# dengen1_2.net
KiCad netlist of a schematic drawn in EAGLE
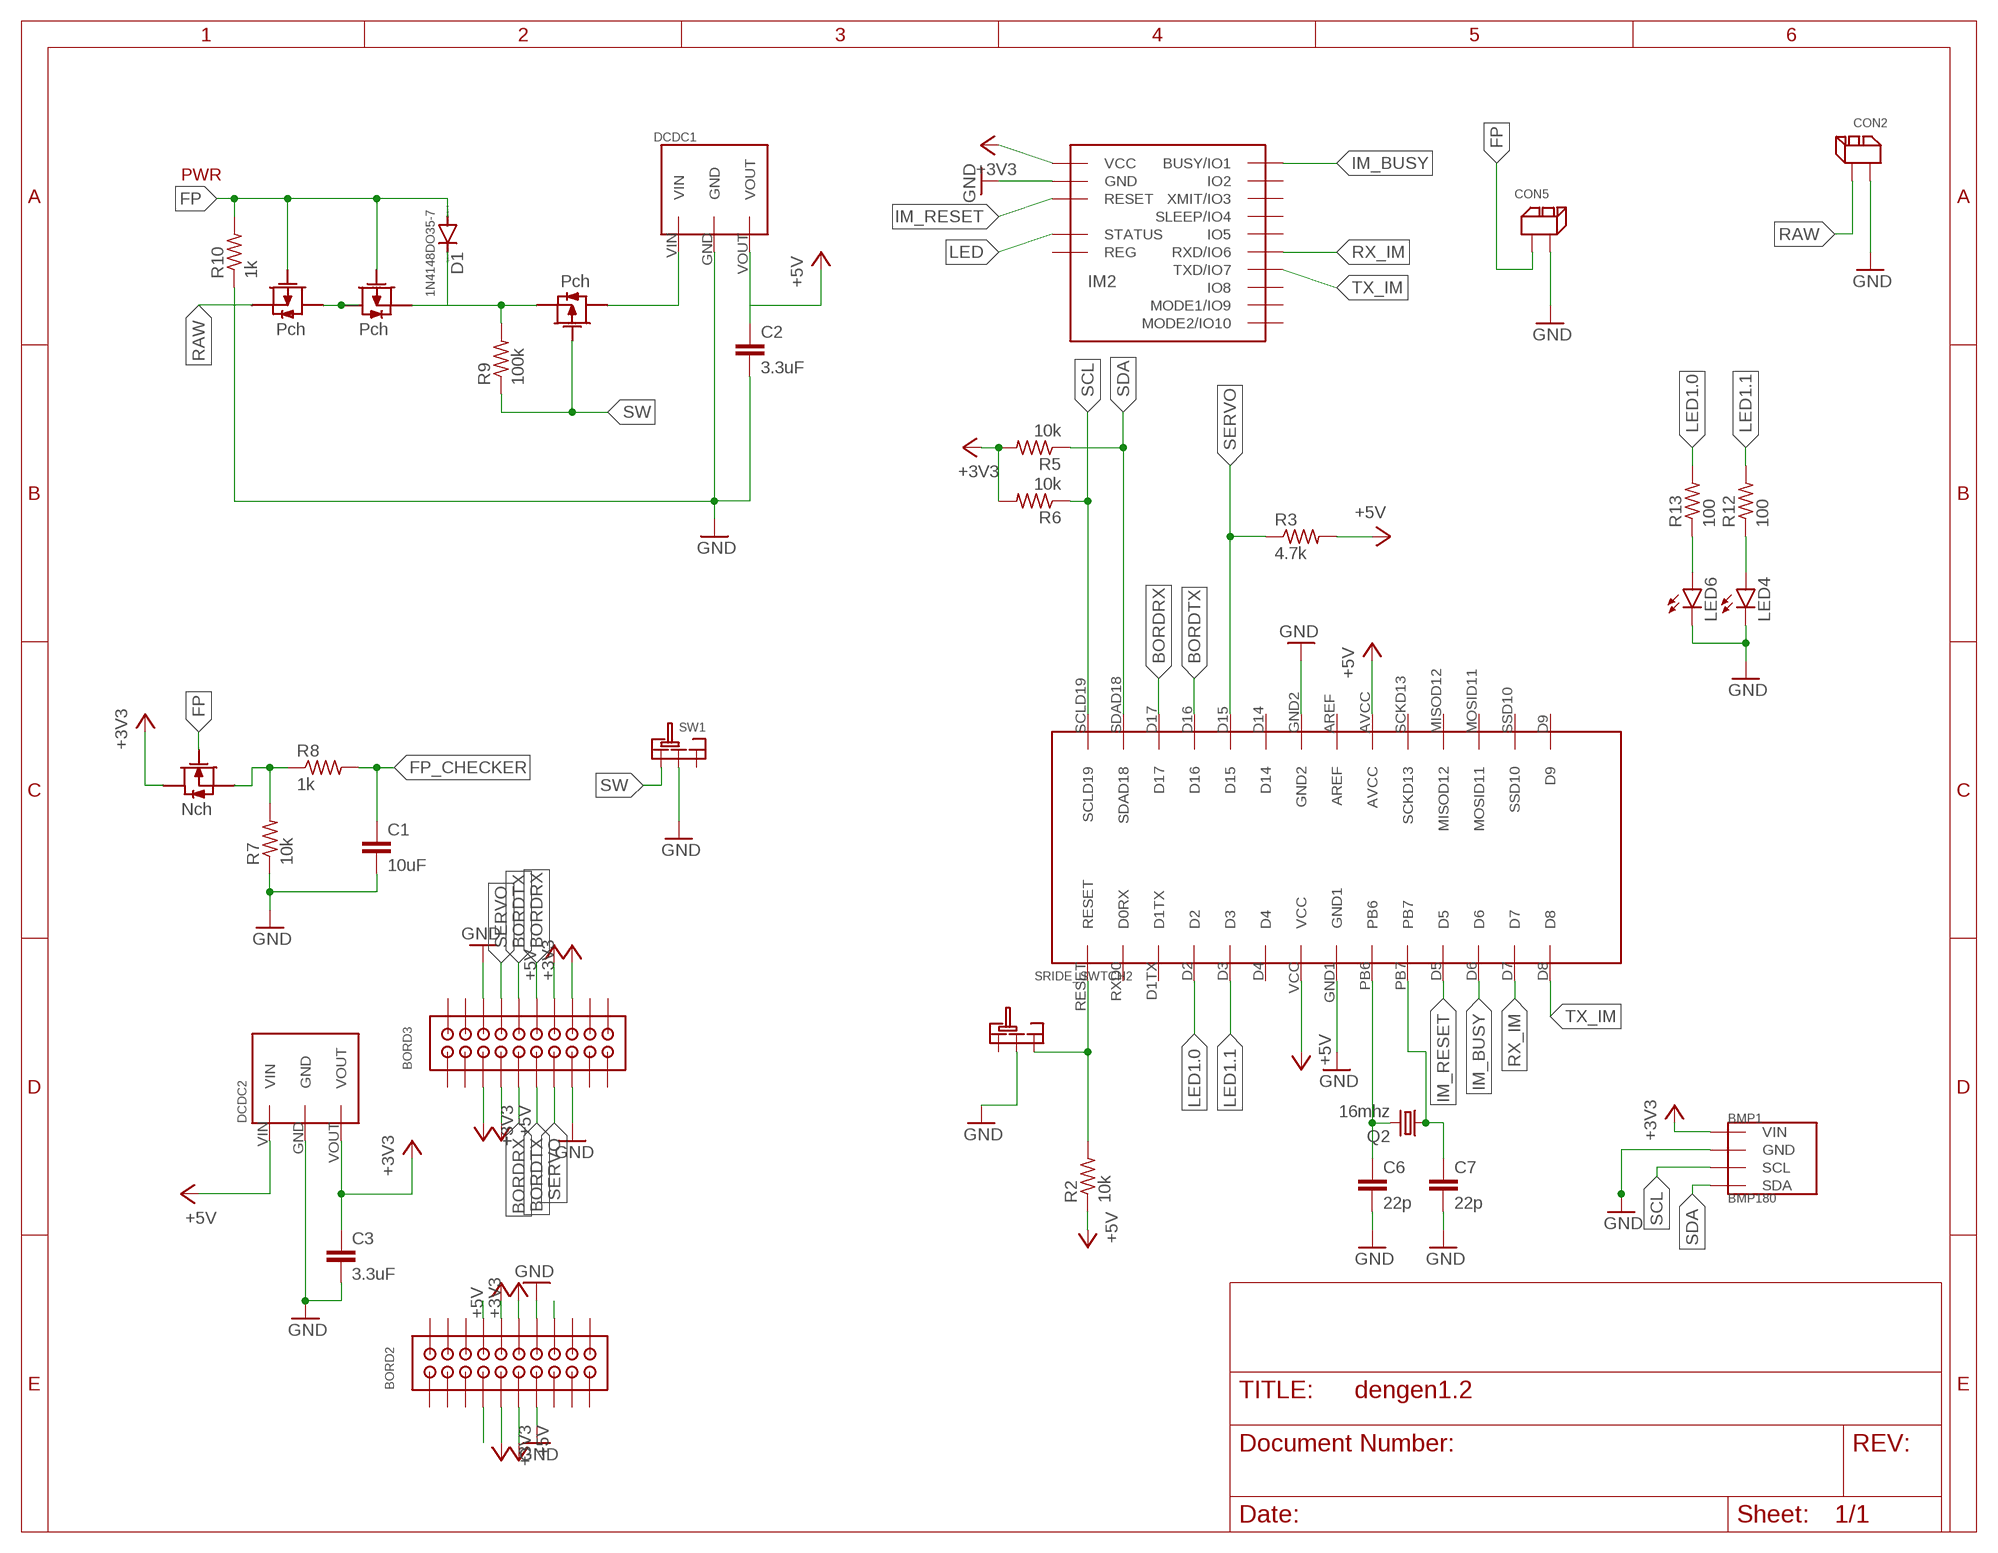
[diagram p0: schematic, sheet 1]

(export (version "E")
  (design (tool "Eeschema 10.0.6"))
  (components
    (comp (ref "BMP1")
      (value "BMP180")
      (footprint "eagle-import:GY-68")
      (libsource (lib "eagle-import") (part "BMP180"))
    )
    (comp (ref "BORD2")
      (value "2X10")
      (footprint "eagle-import:2X10")
      (libsource (lib "eagle-import") (part "2X10"))
    )
    (comp (ref "BORD3")
      (value "2X10")
      (footprint "eagle-import:2X10")
      (libsource (lib "eagle-import") (part "2X10"))
    )
    (comp (ref "C1")
      (value "10uF")
      (footprint "eagle-import:C025-024X044")
      (libsource (lib "eagle-import") (part "C-EU025-024X044"))
    )
    (comp (ref "C2")
      (value "3.3uF")
      (footprint "eagle-import:C025-024X044")
      (libsource (lib "eagle-import") (part "C-EU025-024X044"))
    )
    (comp (ref "C3")
      (value "3.3uF")
      (footprint "eagle-import:C025-024X044")
      (libsource (lib "eagle-import") (part "C-EU025-024X044"))
    )
    (comp (ref "C6")
      (value "22p")
      (footprint "eagle-import:C025-024X044")
      (libsource (lib "eagle-import") (part "C-EU025-024X044"))
    )
    (comp (ref "C7")
      (value "22p")
      (footprint "eagle-import:C025-024X044")
      (libsource (lib "eagle-import") (part "C-EU025-024X044"))
    )
    (comp (ref "CON2")
      (value "2PIN")
      (footprint "eagle-import:2PIN")
      (libsource (lib "eagle-import") (part "2PIN"))
    )
    (comp (ref "CON5")
      (value "2PIN")
      (footprint "eagle-import:2PIN")
      (libsource (lib "eagle-import") (part "2PIN"))
    )
    (comp (ref "D1")
      (value "1N4148DO35-7")
      (footprint "eagle-import:DO35-7")
      (libsource (lib "eagle-import") (part "1N4148DO35-7"))
    )
    (comp (ref "DCDC1")
      (value "5V1A_M78AR05-1")
      (footprint "eagle-import:5V1A_M78AR05-1")
      (libsource (lib "eagle-import") (part "5V1A_M78AR05-1"))
    )
    (comp (ref "DCDC2")
      (value "3.3V1A_M78AR033-1")
      (footprint "eagle-import:3.3V1A_M78AR033-1")
      (libsource (lib "eagle-import") (part "3.3V1A_M78AR033-1"))
    )
    (comp (ref "IM2")
      (value "IM920_IM920C")
      (footprint "eagle-import:IM920_IM920C")
      (libsource (lib "eagle-import") (part "IM920_IM920C"))
    )
    (comp (ref "LED4")
      (value "LED5MM")
      (footprint "eagle-import:LED5MM")
      (libsource (lib "eagle-import") (part "LED5MM"))
    )
    (comp (ref "LED6")
      (value "LED5MM")
      (footprint "eagle-import:LED5MM")
      (libsource (lib "eagle-import") (part "LED5MM"))
    )
    (comp (ref "Q2")
      (value "16mhz")
      (footprint "eagle-import:HC49_S")
      (libsource (lib "eagle-import") (part "CRYSTALHC49S"))
    )
    (comp (ref "R2")
      (value "10k")
      (footprint "eagle-import:0204_7")
      (libsource (lib "eagle-import") (part "R-US_0204/7"))
    )
    (comp (ref "R3")
      (value "4.7k")
      (footprint "eagle-import:0204_7")
      (libsource (lib "eagle-import") (part "R-US_0204/7"))
    )
    (comp (ref "R5")
      (value "10k")
      (footprint "eagle-import:0204_7")
      (libsource (lib "eagle-import") (part "R-US_0204/7"))
    )
    (comp (ref "R6")
      (value "10k")
      (footprint "eagle-import:0204_7")
      (libsource (lib "eagle-import") (part "R-US_0204/7"))
    )
    (comp (ref "R7")
      (value "10k")
      (footprint "eagle-import:0204_7")
      (libsource (lib "eagle-import") (part "R-US_0204/7"))
    )
    (comp (ref "R8")
      (value "1k")
      (footprint "eagle-import:0204_7")
      (libsource (lib "eagle-import") (part "R-US_0204/7"))
    )
    (comp (ref "R9")
      (value "100k")
      (footprint "eagle-import:0204_7")
      (libsource (lib "eagle-import") (part "R-US_0204/7"))
    )
    (comp (ref "R10")
      (value "1k")
      (footprint "eagle-import:0204_7")
      (libsource (lib "eagle-import") (part "R-US_0204/7"))
    )
    (comp (ref "R12")
      (value "100")
      (footprint "eagle-import:0204_7")
      (libsource (lib "eagle-import") (part "R-US_0204/7"))
    )
    (comp (ref "R13")
      (value "100")
      (footprint "eagle-import:0204_7")
      (libsource (lib "eagle-import") (part "R-US_0204/7"))
    )
    (comp (ref "SRIDE_SWTCH2")
      (value "SRIDE_SWITCH")
      (footprint "eagle-import:SRIDE_SWITCH")
      (libsource (lib "eagle-import") (part "SRIDE_SWITCH"))
    )
    (comp (ref "SW1")
      (value "SRIDE_SWITCH")
      (footprint "eagle-import:SRIDE_SWITCH")
      (libsource (lib "eagle-import") (part "SRIDE_SWITCH"))
    )
    (comp (ref "U$2")
      (value "2SJ681-PCH")
      (footprint "eagle-import:2SJ681")
      (libsource (lib "eagle-import") (part "2SJ681-PCH"))
    )
    (comp (ref "U$3")
      (value "2SK4017-NCH")
      (footprint "eagle-import:2SK4017")
      (libsource (lib "eagle-import") (part "2SK4017-NCH"))
    )
    (comp (ref "U$4")
      (value "2SJ681-PCH")
      (footprint "eagle-import:2SJ681")
      (libsource (lib "eagle-import") (part "2SJ681-PCH"))
    )
    (comp (ref "U$5")
      (value "2SJ681-PCH")
      (footprint "eagle-import:2SJ681")
      (libsource (lib "eagle-import") (part "2SJ681-PCH"))
    )
    (comp (ref "U$6")
      (value "ATMEGA238P")
      (footprint "eagle-import:ATMEGA328P")
      (libsource (lib "eagle-import") (part "ATMEGA238P"))
    )
  )
  (nets
    (net (code "1") (name "+3V3") (class "Default")
      (node (ref "BMP1") (pin "P1") (pinfunction "VIN_P1") (pintype "bidirectional"))
      (node (ref "BORD2") (pin "P$12") (pinfunction "P$12_P$12") (pintype "bidirectional"))
      (node (ref "BORD2") (pin "P$9") (pinfunction "P$9_P$9") (pintype "bidirectional"))
      (node (ref "BORD3") (pin "P$16") (pinfunction "P$16_P$16") (pintype "bidirectional"))
      (node (ref "BORD3") (pin "P$5") (pinfunction "P$5_P$5") (pintype "bidirectional"))
      (node (ref "C3") (pin "1") (pinfunction "1_1") (pintype "passive"))
      (node (ref "DCDC2") (pin "VOUT") (pinfunction "VOUT_VOUT") (pintype "bidirectional"))
      (node (ref "IM2") (pin "$P17") (pinfunction "VCC_$P17") (pintype "bidirectional"))
      (node (ref "R5") (pin "2") (pinfunction "2_2") (pintype "passive"))
      (node (ref "R6") (pin "2") (pinfunction "2_2") (pintype "passive"))
      (node (ref "U$3") (pin "DRAIN") (pinfunction "DRAIN_DRAIN") (pintype "bidirectional"))
    )
    (net (code "2") (name "+5V") (class "Default")
      (node (ref "BORD2") (pin "P$10") (pinfunction "P$10_P$10") (pintype "bidirectional"))
      (node (ref "BORD2") (pin "P$11") (pinfunction "P$11_P$11") (pintype "bidirectional"))
      (node (ref "BORD3") (pin "P$14") (pinfunction "P$14_P$14") (pintype "bidirectional"))
      (node (ref "BORD3") (pin "P$7") (pinfunction "P$7_P$7") (pintype "bidirectional"))
      (node (ref "C2") (pin "1") (pinfunction "1_1") (pintype "passive"))
      (node (ref "DCDC1") (pin "VOUT") (pinfunction "VOUT_VOUT") (pintype "bidirectional"))
      (node (ref "DCDC2") (pin "VIN") (pinfunction "VIN_VIN") (pintype "bidirectional"))
      (node (ref "R2") (pin "1") (pinfunction "1_1") (pintype "passive"))
      (node (ref "R3") (pin "2") (pinfunction "2_2") (pintype "passive"))
      (node (ref "U$6") (pin "AVCC") (pinfunction "AVCC_AVCC") (pintype "bidirectional"))
      (node (ref "U$6") (pin "VCC") (pinfunction "VCC_VCC") (pintype "bidirectional"))
    )
    (net (code "3") (name "BORDRX") (class "Default")
      (node (ref "BORD3") (pin "P$12") (pinfunction "P$12_P$12") (pintype "bidirectional"))
      (node (ref "BORD3") (pin "P$9") (pinfunction "P$9_P$9") (pintype "bidirectional"))
      (node (ref "U$6") (pin "D17") (pinfunction "D17_D17") (pintype "bidirectional"))
    )
    (net (code "4") (name "BORDTX") (class "Default")
      (node (ref "BORD3") (pin "P$10") (pinfunction "P$10_P$10") (pintype "bidirectional"))
      (node (ref "BORD3") (pin "P$11") (pinfunction "P$11_P$11") (pintype "bidirectional"))
      (node (ref "U$6") (pin "D16") (pinfunction "D16_D16") (pintype "bidirectional"))
    )
    (net (code "5") (name "FP") (class "Default")
      (node (ref "CON5") (pin "P$1") (pinfunction "P$1_P$1") (pintype "bidirectional"))
      (node (ref "D1") (pin "A") (pinfunction "A_A") (pintype "passive"))
      (node (ref "R10") (pin "2") (pinfunction "2_2") (pintype "passive"))
      (node (ref "U$2") (pin "GATE") (pinfunction "GATE_GATE") (pintype "bidirectional"))
      (node (ref "U$3") (pin "GATE") (pinfunction "GATE_GATE") (pintype "bidirectional"))
      (node (ref "U$4") (pin "GATE") (pinfunction "GATE_GATE") (pintype "bidirectional"))
    )
    (net (code "6") (name "FP_CHECKER") (class "Default")
      (node (ref "C1") (pin "1") (pinfunction "1_1") (pintype "passive"))
      (node (ref "R8") (pin "2") (pinfunction "2_2") (pintype "passive"))
    )
    (net (code "7") (name "GND") (class "Default")
      (node (ref "BMP1") (pin "P2") (pinfunction "GND_P2") (pintype "bidirectional"))
      (node (ref "BORD2") (pin "P$13") (pinfunction "P$13_P$13") (pintype "bidirectional"))
      (node (ref "BORD2") (pin "P$14") (pinfunction "P$14_P$14") (pintype "bidirectional"))
      (node (ref "BORD3") (pin "P$15") (pinfunction "P$15_P$15") (pintype "bidirectional"))
      (node (ref "BORD3") (pin "P$6") (pinfunction "P$6_P$6") (pintype "bidirectional"))
      (node (ref "C1") (pin "2") (pinfunction "2_2") (pintype "passive"))
      (node (ref "C2") (pin "2") (pinfunction "2_2") (pintype "passive"))
      (node (ref "C3") (pin "2") (pinfunction "2_2") (pintype "passive"))
      (node (ref "C6") (pin "2") (pinfunction "2_2") (pintype "passive"))
      (node (ref "C7") (pin "2") (pinfunction "2_2") (pintype "passive"))
      (node (ref "CON2") (pin "P$1") (pinfunction "P$1_P$1") (pintype "bidirectional"))
      (node (ref "CON5") (pin "P$2") (pinfunction "P$2_P$2") (pintype "bidirectional"))
      (node (ref "DCDC1") (pin "GND") (pinfunction "GND_GND") (pintype "bidirectional"))
      (node (ref "DCDC2") (pin "GND") (pinfunction "GND_GND") (pintype "bidirectional"))
      (node (ref "IM2") (pin "$P18") (pinfunction "GND_$P18") (pintype "bidirectional"))
      (node (ref "LED4") (pin "K") (pinfunction "C_K") (pintype "passive"))
      (node (ref "LED6") (pin "K") (pinfunction "C_K") (pintype "passive"))
      (node (ref "R10") (pin "1") (pinfunction "1_1") (pintype "passive"))
      (node (ref "R7") (pin "1") (pinfunction "1_1") (pintype "passive"))
      (node (ref "SRIDE_SWTCH2") (pin "LR") (pinfunction "LR_LR") (pintype "bidirectional"))
      (node (ref "SW1") (pin "LR") (pinfunction "LR_LR") (pintype "bidirectional"))
      (node (ref "U$6") (pin "GND1") (pinfunction "GND1_GND1") (pintype "bidirectional"))
      (node (ref "U$6") (pin "GND2") (pinfunction "GND2_GND2") (pintype "bidirectional"))
    )
    (net (code "8") (name "IM_BUSY") (class "Default")
      (node (ref "IM2") (pin "$P1") (pinfunction "BUSY/IO1_$P1") (pintype "bidirectional"))
      (node (ref "U$6") (pin "D6") (pinfunction "D6_D6") (pintype "bidirectional"))
    )
    (net (code "9") (name "IM_RESET") (class "Default")
      (node (ref "IM2") (pin "$P19") (pinfunction "RESET_$P19") (pintype "bidirectional"))
      (node (ref "U$6") (pin "D5") (pinfunction "D5_D5") (pintype "bidirectional"))
    )
    (net (code "10") (name "LED") (class "Default")
      (node (ref "IM2") (pin "$P15") (pinfunction "STATUS_$P15") (pintype "bidirectional"))
    )
    (net (code "11") (name "LED1.0") (class "Default")
      (node (ref "R13") (pin "2") (pinfunction "2_2") (pintype "passive"))
      (node (ref "U$6") (pin "D2") (pinfunction "D2_D2") (pintype "bidirectional"))
    )
    (net (code "12") (name "LED1.1") (class "Default")
      (node (ref "R12") (pin "2") (pinfunction "2_2") (pintype "passive"))
      (node (ref "U$6") (pin "D3") (pinfunction "D3_D3") (pintype "bidirectional"))
    )
    (net (code "13") (name "Net-(C6-Pad1)") (class "Default")
      (node (ref "C6") (pin "1") (pinfunction "1_1") (pintype "passive"))
      (node (ref "Q2") (pin "2") (pinfunction "2_2") (pintype "passive"))
      (node (ref "U$6") (pin "PB6") (pinfunction "PB6_PB6") (pintype "bidirectional"))
    )
    (net (code "14") (name "Net-(C7-Pad1)") (class "Default")
      (node (ref "C7") (pin "1") (pinfunction "1_1") (pintype "passive"))
      (node (ref "Q2") (pin "1") (pinfunction "1_1") (pintype "passive"))
      (node (ref "U$6") (pin "PB7") (pinfunction "PB7_PB7") (pintype "bidirectional"))
    )
    (net (code "15") (name "Net-(D1-PadC)") (class "Default")
      (node (ref "D1") (pin "C") (pinfunction "C_C") (pintype "passive"))
      (node (ref "R9") (pin "2") (pinfunction "2_2") (pintype "passive"))
      (node (ref "U$4") (pin "SOURCE") (pinfunction "SOURCE_SOURCE") (pintype "bidirectional"))
      (node (ref "U$5") (pin "SOURCE") (pinfunction "SOURCE_SOURCE") (pintype "bidirectional"))
    )
    (net (code "16") (name "Net-(DCDC1-PadVIN)") (class "Default")
      (node (ref "DCDC1") (pin "VIN") (pinfunction "VIN_VIN") (pintype "bidirectional"))
      (node (ref "U$5") (pin "DRAIN") (pinfunction "DRAIN_DRAIN") (pintype "bidirectional"))
    )
    (net (code "17") (name "Net-(LED4-PadA)") (class "Default")
      (node (ref "LED4") (pin "A") (pinfunction "A_A") (pintype "passive"))
      (node (ref "R12") (pin "1") (pinfunction "1_1") (pintype "passive"))
    )
    (net (code "18") (name "Net-(LED6-PadA)") (class "Default")
      (node (ref "LED6") (pin "A") (pinfunction "A_A") (pintype "passive"))
      (node (ref "R13") (pin "1") (pinfunction "1_1") (pintype "passive"))
    )
    (net (code "19") (name "Net-(R2-Pad2)") (class "Default")
      (node (ref "R2") (pin "2") (pinfunction "2_2") (pintype "passive"))
      (node (ref "SRIDE_SWTCH2") (pin "R") (pinfunction "R_R") (pintype "bidirectional"))
      (node (ref "U$6") (pin "RESET") (pinfunction "RESET_RESET") (pintype "bidirectional"))
    )
    (net (code "20") (name "Net-(R7-Pad2)") (class "Default")
      (node (ref "R7") (pin "2") (pinfunction "2_2") (pintype "passive"))
      (node (ref "R8") (pin "1") (pinfunction "1_1") (pintype "passive"))
      (node (ref "U$3") (pin "SOURCE") (pinfunction "SOURCE_SOURCE") (pintype "bidirectional"))
    )
    (net (code "21") (name "Net-(U$2-PadDRAIN)") (class "Default")
      (node (ref "U$2") (pin "DRAIN") (pinfunction "DRAIN_DRAIN") (pintype "bidirectional"))
      (node (ref "U$4") (pin "DRAIN") (pinfunction "DRAIN_DRAIN") (pintype "bidirectional"))
    )
    (net (code "22") (name "RAW") (class "Default")
      (node (ref "CON2") (pin "P$2") (pinfunction "P$2_P$2") (pintype "bidirectional"))
      (node (ref "U$2") (pin "SOURCE") (pinfunction "SOURCE_SOURCE") (pintype "bidirectional"))
    )
    (net (code "23") (name "RX_IM") (class "Default")
      (node (ref "IM2") (pin "$P6") (pinfunction "RXD/IO6_$P6") (pintype "bidirectional"))
      (node (ref "U$6") (pin "D7") (pinfunction "D7_D7") (pintype "bidirectional"))
    )
    (net (code "24") (name "SCL") (class "Default")
      (node (ref "BMP1") (pin "P3") (pinfunction "SCL_P3") (pintype "bidirectional"))
      (node (ref "R6") (pin "1") (pinfunction "1_1") (pintype "passive"))
      (node (ref "U$6") (pin "SCLD19") (pinfunction "SCLD19_SCLD19") (pintype "bidirectional"))
    )
    (net (code "25") (name "SDA") (class "Default")
      (node (ref "BMP1") (pin "P4") (pinfunction "SDA_P4") (pintype "bidirectional"))
      (node (ref "R5") (pin "1") (pinfunction "1_1") (pintype "passive"))
      (node (ref "U$6") (pin "SDAD18") (pinfunction "SDAD18_SDAD18") (pintype "bidirectional"))
    )
    (net (code "26") (name "SERVO") (class "Default")
      (node (ref "BORD3") (pin "P$13") (pinfunction "P$13_P$13") (pintype "bidirectional"))
      (node (ref "BORD3") (pin "P$8") (pinfunction "P$8_P$8") (pintype "bidirectional"))
      (node (ref "R3") (pin "1") (pinfunction "1_1") (pintype "passive"))
      (node (ref "U$6") (pin "D15") (pinfunction "D15_D15") (pintype "bidirectional"))
    )
    (net (code "27") (name "SW") (class "Default")
      (node (ref "R9") (pin "1") (pinfunction "1_1") (pintype "passive"))
      (node (ref "SW1") (pin "L") (pinfunction "L_L") (pintype "bidirectional"))
      (node (ref "U$5") (pin "GATE") (pinfunction "GATE_GATE") (pintype "bidirectional"))
    )
    (net (code "28") (name "TX_IM") (class "Default")
      (node (ref "IM2") (pin "$P7") (pinfunction "TXD/IO7_$P7") (pintype "bidirectional"))
      (node (ref "U$6") (pin "D8") (pinfunction "D8_D8") (pintype "bidirectional"))
    )
    (net (code "29") (name "unconnected-(BORD2-PadP$1)") (class "Default")
      (node (ref "BORD2") (pin "P$1") (pinfunction "P$1_P$1") (pintype "bidirectional"))
    )
    (net (code "30") (name "unconnected-(BORD2-PadP$2)") (class "Default")
      (node (ref "BORD2") (pin "P$2") (pinfunction "P$2_P$2") (pintype "bidirectional"))
    )
    (net (code "31") (name "unconnected-(BORD2-PadP$3)") (class "Default")
      (node (ref "BORD2") (pin "P$3") (pinfunction "P$3_P$3") (pintype "bidirectional"))
    )
    (net (code "32") (name "unconnected-(BORD2-PadP$4)") (class "Default")
      (node (ref "BORD2") (pin "P$4") (pinfunction "P$4_P$4") (pintype "bidirectional"))
    )
    (net (code "33") (name "unconnected-(BORD2-PadP$5)") (class "Default")
      (node (ref "BORD2") (pin "P$5") (pinfunction "P$5_P$5") (pintype "bidirectional"))
    )
    (net (code "34") (name "unconnected-(BORD2-PadP$6)") (class "Default")
      (node (ref "BORD2") (pin "P$6") (pinfunction "P$6_P$6") (pintype "bidirectional"))
    )
    (net (code "35") (name "unconnected-(BORD2-PadP$7)") (class "Default")
      (node (ref "BORD2") (pin "P$7") (pinfunction "P$7_P$7") (pintype "bidirectional"))
    )
    (net (code "36") (name "unconnected-(BORD2-PadP$8)") (class "Default")
      (node (ref "BORD2") (pin "P$8") (pinfunction "P$8_P$8") (pintype "bidirectional"))
    )
    (net (code "37") (name "unconnected-(BORD2-PadP$15)") (class "Default")
      (node (ref "BORD2") (pin "P$15") (pinfunction "P$15_P$15") (pintype "bidirectional"))
    )
    (net (code "38") (name "unconnected-(BORD2-PadP$16)") (class "Default")
      (node (ref "BORD2") (pin "P$16") (pinfunction "P$16_P$16") (pintype "bidirectional"))
    )
    (net (code "39") (name "unconnected-(BORD2-PadP$17)") (class "Default")
      (node (ref "BORD2") (pin "P$17") (pinfunction "P$17_P$17") (pintype "bidirectional"))
    )
    (net (code "40") (name "unconnected-(BORD2-PadP$18)") (class "Default")
      (node (ref "BORD2") (pin "P$18") (pinfunction "P$18_P$18") (pintype "bidirectional"))
    )
    (net (code "41") (name "unconnected-(BORD2-PadP$19)") (class "Default")
      (node (ref "BORD2") (pin "P$19") (pinfunction "P$19_P$19") (pintype "bidirectional"))
    )
    (net (code "42") (name "unconnected-(BORD2-PadP$20)") (class "Default")
      (node (ref "BORD2") (pin "P$20") (pinfunction "P$20_P$20") (pintype "bidirectional"))
    )
    (net (code "43") (name "unconnected-(BORD3-PadP$1)") (class "Default")
      (node (ref "BORD3") (pin "P$1") (pinfunction "P$1_P$1") (pintype "bidirectional"))
    )
    (net (code "44") (name "unconnected-(BORD3-PadP$2)") (class "Default")
      (node (ref "BORD3") (pin "P$2") (pinfunction "P$2_P$2") (pintype "bidirectional"))
    )
    (net (code "45") (name "unconnected-(BORD3-PadP$3)") (class "Default")
      (node (ref "BORD3") (pin "P$3") (pinfunction "P$3_P$3") (pintype "bidirectional"))
    )
    (net (code "46") (name "unconnected-(BORD3-PadP$4)") (class "Default")
      (node (ref "BORD3") (pin "P$4") (pinfunction "P$4_P$4") (pintype "bidirectional"))
    )
    (net (code "47") (name "unconnected-(BORD3-PadP$17)") (class "Default")
      (node (ref "BORD3") (pin "P$17") (pinfunction "P$17_P$17") (pintype "bidirectional"))
    )
    (net (code "48") (name "unconnected-(BORD3-PadP$18)") (class "Default")
      (node (ref "BORD3") (pin "P$18") (pinfunction "P$18_P$18") (pintype "bidirectional"))
    )
    (net (code "49") (name "unconnected-(BORD3-PadP$19)") (class "Default")
      (node (ref "BORD3") (pin "P$19") (pinfunction "P$19_P$19") (pintype "bidirectional"))
    )
    (net (code "50") (name "unconnected-(BORD3-PadP$20)") (class "Default")
      (node (ref "BORD3") (pin "P$20") (pinfunction "P$20_P$20") (pintype "bidirectional"))
    )
    (net (code "51") (name "unconnected-(IM2-IO2-Pad$P2)") (class "Default")
      (node (ref "IM2") (pin "$P2") (pinfunction "IO2_$P2") (pintype "bidirectional"))
    )
    (net (code "52") (name "unconnected-(IM2-IO5-Pad$P5)") (class "Default")
      (node (ref "IM2") (pin "$P5") (pinfunction "IO5_$P5") (pintype "bidirectional"))
    )
    (net (code "53") (name "unconnected-(IM2-IO8-Pad$P8)") (class "Default")
      (node (ref "IM2") (pin "$P8") (pinfunction "IO8_$P8") (pintype "bidirectional"))
    )
    (net (code "54") (name "unconnected-(IM2-MODE1{slash}IO9-Pad$P9)") (class "Default")
      (node (ref "IM2") (pin "$P9") (pinfunction "MODE1/IO9_$P9") (pintype "bidirectional"))
    )
    (net (code "55") (name "unconnected-(IM2-MODE2{slash}IO10-Pad$P10)") (class "Default")
      (node (ref "IM2") (pin "$P10") (pinfunction "MODE2/IO10_$P10") (pintype "bidirectional"))
    )
    (net (code "56") (name "unconnected-(IM2-REG-Pad$P16)") (class "Default")
      (node (ref "IM2") (pin "$P16") (pinfunction "REG_$P16") (pintype "bidirectional"))
    )
    (net (code "57") (name "unconnected-(IM2-SLEEP{slash}IO4-Pad$P4)") (class "Default")
      (node (ref "IM2") (pin "$P4") (pinfunction "SLEEP/IO4_$P4") (pintype "bidirectional"))
    )
    (net (code "58") (name "unconnected-(IM2-XMIT{slash}IO3-Pad$P3)") (class "Default")
      (node (ref "IM2") (pin "$P3") (pinfunction "XMIT/IO3_$P3") (pintype "bidirectional"))
    )
    (net (code "59") (name "unconnected-(SRIDE_SWTCH2-PadL)") (class "Default")
      (node (ref "SRIDE_SWTCH2") (pin "L") (pinfunction "L_L") (pintype "bidirectional"))
    )
    (net (code "60") (name "unconnected-(SW1-PadR)") (class "Default")
      (node (ref "SW1") (pin "R") (pinfunction "R_R") (pintype "bidirectional"))
    )
    (net (code "61") (name "unconnected-(U$6-D0RX-PadRXD0)") (class "Default")
      (node (ref "U$6") (pin "RXD0") (pinfunction "D0RX_RXD0") (pintype "bidirectional"))
    )
    (net (code "62") (name "unconnected-(U$6-PadAREF)") (class "Default")
      (node (ref "U$6") (pin "AREF") (pinfunction "AREF_AREF") (pintype "bidirectional"))
    )
    (net (code "63") (name "unconnected-(U$6-PadD1TX)") (class "Default")
      (node (ref "U$6") (pin "D1TX") (pinfunction "D1TX_D1TX") (pintype "bidirectional"))
    )
    (net (code "64") (name "unconnected-(U$6-PadD4)") (class "Default")
      (node (ref "U$6") (pin "D4") (pinfunction "D4_D4") (pintype "bidirectional"))
    )
    (net (code "65") (name "unconnected-(U$6-PadD9)") (class "Default")
      (node (ref "U$6") (pin "D9") (pinfunction "D9_D9") (pintype "bidirectional"))
    )
    (net (code "66") (name "unconnected-(U$6-PadD14)") (class "Default")
      (node (ref "U$6") (pin "D14") (pinfunction "D14_D14") (pintype "bidirectional"))
    )
    (net (code "67") (name "unconnected-(U$6-PadMISOD12)") (class "Default")
      (node (ref "U$6") (pin "MISOD12") (pinfunction "MISOD12_MISOD12") (pintype "bidirectional"))
    )
    (net (code "68") (name "unconnected-(U$6-PadMOSID11)") (class "Default")
      (node (ref "U$6") (pin "MOSID11") (pinfunction "MOSID11_MOSID11") (pintype "bidirectional"))
    )
    (net (code "69") (name "unconnected-(U$6-PadSCKD13)") (class "Default")
      (node (ref "U$6") (pin "SCKD13") (pinfunction "SCKD13_SCKD13") (pintype "bidirectional"))
    )
    (net (code "70") (name "unconnected-(U$6-PadSSD10)") (class "Default")
      (node (ref "U$6") (pin "SSD10") (pinfunction "SSD10_SSD10") (pintype "bidirectional"))
    )
  )
)
